# LaserModulev1_1.net
KiCad netlist of a schematic drawn in EAGLE
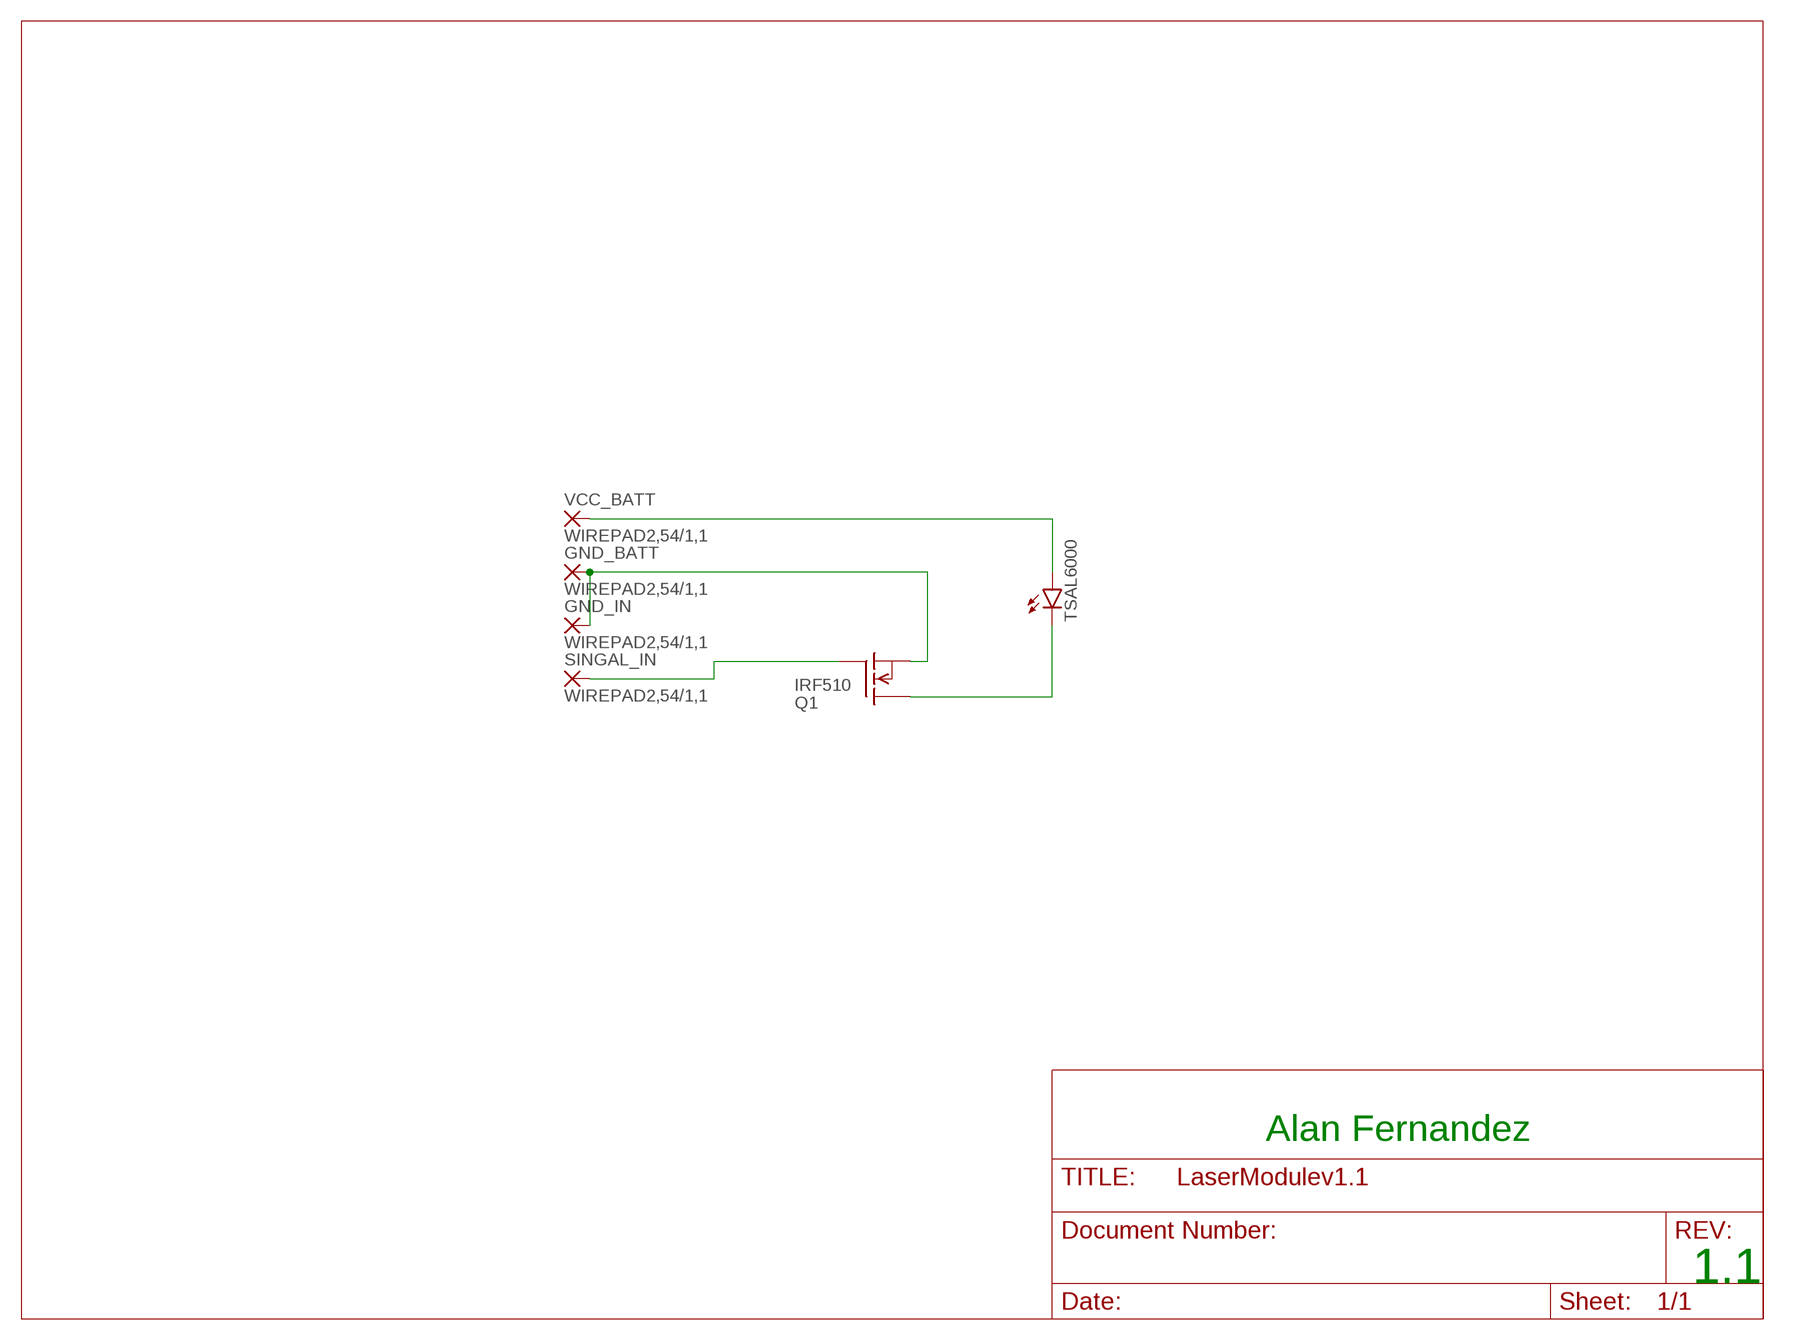
[diagram p0: schematic, sheet 1]

(export (version "E")
  (design (tool "Eeschema 10.0.6"))
  (components
    (comp (ref "GND_BATT")
      (value "WIREPAD2,54/1,1")
      (footprint "eagle-import:2,54_1,1")
      (libsource (lib "eagle-import") (part "WIREPAD2,54/1,1"))
    )
    (comp (ref "GND_IN")
      (value "WIREPAD2,54/1,1")
      (footprint "eagle-import:2,54_1,1")
      (libsource (lib "eagle-import") (part "WIREPAD2,54/1,1"))
    )
    (comp (ref "Q1")
      (value "IRF510")
      (footprint "eagle-import:TO220")
      (libsource (lib "eagle-import") (part "IRF510"))
    )
    (comp (ref "SINGAL_IN")
      (value "WIREPAD2,54/1,1")
      (footprint "eagle-import:2,54_1,1")
      (libsource (lib "eagle-import") (part "WIREPAD2,54/1,1"))
    )
    (comp (ref "TSAL6000")
      (value "LED5MM")
      (footprint "eagle-import:LED5MM")
      (libsource (lib "eagle-import") (part "LED5MM"))
    )
    (comp (ref "VCC_BATT")
      (value "WIREPAD2,54/1,1")
      (footprint "eagle-import:2,54_1,1")
      (libsource (lib "eagle-import") (part "WIREPAD2,54/1,1"))
    )
  )
  (nets
    (net (code "1") (name "Net-(GND_BATT-P)") (class "Default")
      (node (ref "GND_BATT") (pin "1") (pinfunction "P_1") (pintype "passive"))
      (node (ref "GND_IN") (pin "1") (pinfunction "P_1") (pintype "passive"))
      (node (ref "Q1") (pin "3") (pinfunction "S_3") (pintype "passive"))
    )
    (net (code "2") (name "Net-(Q1-D)") (class "Default")
      (node (ref "Q1") (pin "2") (pinfunction "D_2") (pintype "passive"))
      (node (ref "TSAL6000") (pin "K") (pinfunction "C_K") (pintype "passive"))
    )
    (net (code "3") (name "Net-(Q1-G)") (class "Default")
      (node (ref "Q1") (pin "1") (pinfunction "G_1") (pintype "passive"))
      (node (ref "SINGAL_IN") (pin "1") (pinfunction "P_1") (pintype "passive"))
    )
    (net (code "4") (name "Net-(VCC_BATT-P)") (class "Default")
      (node (ref "TSAL6000") (pin "A") (pinfunction "A_A") (pintype "passive"))
      (node (ref "VCC_BATT") (pin "1") (pinfunction "P_1") (pintype "passive"))
    )
  )
)
